# 05_Power.net
KiCad netlist of a schematic drawn in Altium Designer
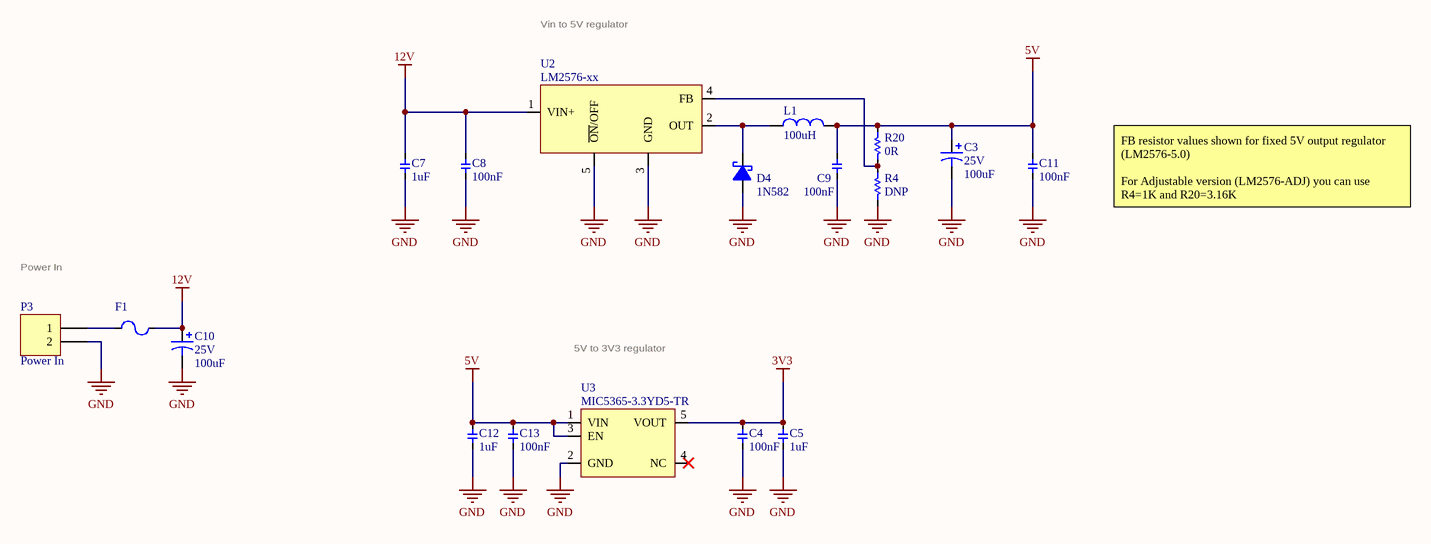
[diagram p0: 05_Power.SchDoc]

(export (version "E")
  (design (tool "Eeschema 10.0.6"))
  (components
    (comp (ref "C3")
      (value "25V")
      (footprint "Footprint_Misc:Electrolytic Cap 2.54mm")
      (description "Polarized Capacitor (Axial)")
      (fields
        (field (name "MANUFACTURER") "Würth Elektronik")
        (field (name "MANUFACTURER PART NUMBER") "860160674021")
        (field (name "ALTIUM_VALUE") "100uF")
      )
      (libsource (lib "Schematic_Misc") (part "Cap Electrolytic"))
    )
    (comp (ref "C4")
      (value "100nF")
      (footprint "Footprint_Misc:0603 - CAP")
      (description "Capacitor")
      (fields
        (field (name "MANUFACTURER") "Samsung Electro-Mechanics")
        (field (name "MANUFACTURER PART NUMBER") "CL10B103KB8NNNC")
      )
      (libsource (lib "Schematic_Misc") (part "Cap"))
    )
    (comp (ref "C5")
      (value "1uF")
      (footprint "Footprint_Misc:0603 - CAP")
      (description "Capacitor")
      (fields
        (field (name "MANUFACTURER") "Samsung Electro-Mechanics")
        (field (name "MANUFACTURER PART NUMBER") "CL10A105KB8NNNC")
      )
      (libsource (lib "Schematic_Misc") (part "Cap"))
    )
    (comp (ref "C7")
      (value "1uF")
      (footprint "Footprint_Misc:0603 - CAP")
      (description "Capacitor")
      (fields
        (field (name "MANUFACTURER") "Samsung Electro-Mechanics")
        (field (name "MANUFACTURER PART NUMBER") "CL10A105KB8NNNC")
      )
      (libsource (lib "Schematic_Misc") (part "Cap"))
    )
    (comp (ref "C8")
      (value "100nF")
      (footprint "Footprint_Misc:0603 - CAP")
      (description "Capacitor")
      (fields
        (field (name "MANUFACTURER") "Samsung Electro-Mechanics")
        (field (name "MANUFACTURER PART NUMBER") "CL10B103KB8NNNC")
      )
      (libsource (lib "Schematic_Misc") (part "Cap"))
    )
    (comp (ref "C9")
      (value "100nF")
      (footprint "Footprint_Misc:0603 - CAP")
      (description "Capacitor")
      (fields
        (field (name "MANUFACTURER") "Samsung Electro-Mechanics")
        (field (name "MANUFACTURER PART NUMBER") "CL10B103KB8NNNC")
      )
      (libsource (lib "Schematic_Misc") (part "Cap"))
    )
    (comp (ref "C10")
      (value "25V")
      (footprint "Footprint_Misc:Electrolytic Cap 2.54mm")
      (description "Polarized Capacitor (Axial)")
      (fields
        (field (name "MANUFACTURER") "Würth Elektronik")
        (field (name "MANUFACTURER PART NUMBER") "860160674021")
        (field (name "ALTIUM_VALUE") "100uF")
      )
      (libsource (lib "Schematic_Misc") (part "Cap Electrolytic"))
    )
    (comp (ref "C11")
      (value "100nF")
      (footprint "Footprint_Misc:0603 - CAP")
      (description "Capacitor")
      (fields
        (field (name "MANUFACTURER") "Samsung Electro-Mechanics")
        (field (name "MANUFACTURER PART NUMBER") "CL10B103KB8NNNC")
      )
      (libsource (lib "Schematic_Misc") (part "Cap"))
    )
    (comp (ref "C12")
      (value "1uF")
      (footprint "Footprint_Misc:0603 - CAP")
      (description "Capacitor")
      (fields
        (field (name "MANUFACTURER") "Samsung Electro-Mechanics")
        (field (name "MANUFACTURER PART NUMBER") "CL10A105KB8NNNC")
      )
      (libsource (lib "Schematic_Misc") (part "Cap"))
    )
    (comp (ref "C13")
      (value "100nF")
      (footprint "Footprint_Misc:0603 - CAP")
      (description "Capacitor")
      (fields
        (field (name "MANUFACTURER") "Samsung Electro-Mechanics")
        (field (name "MANUFACTURER PART NUMBER") "CL10B103KB8NNNC")
      )
      (libsource (lib "Schematic_Misc") (part "Cap"))
    )
    (comp (ref "D4")
      (value "1N582")
      (footprint "Moji Footprintovi:SOD123F")
      (fields
        (field (name "MANUFACTURER") "Nexperia USA Inc.")
        (field (name "MANUFACTURER PART NUMBER") "PMEG6010CEH,115")
        (field (name "DISTRIBUTOR PART NUMBER") "1727-3848-1-ND")
      )
      (libsource (lib "Moji Schematici (1)") (part "Diode Schotky"))
    )
    (comp (ref "F1")
      (value "Fuse Thermal")
      (footprint "Moji Footprintovi:1812F")
      (description "Thermal Fuse")
      (fields
        (field (name "DISTRIBUTOR PART NUMBER") "SF-1206SP200-2CT-ND")
        (field (name "MANUFACTURER") "Bourns Inc.")
      )
      (libsource (lib "Moji Schematici (1)") (part "Fuse Thermal"))
    )
    (comp (ref "L1")
      (value "100uH")
      (footprint "Moji Footprintovi:IND_TH_SMD")
      (description "Inductor")
      (fields
        (field (name "MANUFACTURER") "TDK Corporation")
        (field (name "MANUFACTURER PART NUMBER") "VLS6045AF-101M")
      )
      (libsource (lib "Schematic_Misc") (part "Inductor"))
    )
    (comp (ref "P3")
      (value "Power In")
      (footprint "Moji Footprintovi:Header 2x1")
      (description "Header, 2-Pin")
      (libsource (lib "Moji Schematici (1)") (part "Header 2"))
    )
    (comp (ref "R4")
      (value "DNP")
      (footprint "Footprint_Misc:0603 - HS")
      (description "Resistor")
      (fields (field (name "Comment") "Res"))
      (libsource (lib "Moji Schematici (1)") (part "Res"))
    )
    (comp (ref "R20")
      (value "0R")
      (footprint "Footprint_Misc:0603 - HS")
      (description "Resistor")
      (fields
        (field (name "DISTRIBUTOR PART NUMBER") "RMCF0603ZT0R00CT-ND")
        (field (name "MANUFACTURER") "Stackpole Electronics Inc")
      )
      (libsource (lib "Moji Schematici (1)") (part "Res"))
    )
    (comp (ref "U2")
      (value "LM2576-xx")
      (footprint "Footprint_Misc:TO263-5")
      (description "Switching mode regulator [ 3v3, 5v, 12v and ADJ ]")
      (fields
        (field (name "DISTRIBUTOR PART NUMBER") "LM2576S-5.0/NOPB-ND")
        (field (name "MANUFACTURER") "Texas Instruments")
      )
      (libsource (lib "Schematic_Misc") (part "LM2576-xx"))
    )
    (comp (ref "U3")
      (value "MIC5365-3.3YD5-TR")
      (footprint "Moji Footprintovi:SOT-23-5 - duplicate")
      (description "IC REG LIN 3.3V 150MA TSOT23-5")
      (fields
        (field (name "DISTRIBUTOR PART NUMBER") "576-4085-1-ND")
        (field (name "MANUFACTURER") "Microchip Technology")
      )
      (libsource (lib "Schematic_Misc") (part "MIC5365-1.8YD5-TR"))
    )
  )
  (nets
    (net (code "1") (name "3V3") (class "Default")
      (node (ref "C4") (pin "2") (pinfunction "2_2") (pintype "passive"))
      (node (ref "C5") (pin "2") (pinfunction "2_2") (pintype "passive"))
      (node (ref "U3") (pin "5") (pinfunction "VOUT_5") (pintype "passive"))
    )
    (net (code "2") (name "5V") (class "Default")
      (node (ref "C11") (pin "2") (pinfunction "2_2") (pintype "passive"))
      (node (ref "C12") (pin "2") (pinfunction "2_2") (pintype "passive"))
      (node (ref "C13") (pin "2") (pinfunction "2_2") (pintype "passive"))
      (node (ref "C3") (pin "1") (pinfunction "1_1") (pintype "passive"))
      (node (ref "C9") (pin "2") (pinfunction "2_2") (pintype "passive"))
      (node (ref "L1") (pin "2") (pinfunction "2_2") (pintype "passive"))
      (node (ref "R20") (pin "2") (pinfunction "2_2") (pintype "passive"))
      (node (ref "U3") (pin "1") (pinfunction "VIN_1") (pintype "passive"))
      (node (ref "U3") (pin "3") (pinfunction "EN_3") (pintype "passive"))
    )
    (net (code "3") (name "12V") (class "Default")
      (node (ref "C10") (pin "1") (pinfunction "1_1") (pintype "passive"))
      (node (ref "C7") (pin "2") (pinfunction "2_2") (pintype "passive"))
      (node (ref "C8") (pin "2") (pinfunction "2_2") (pintype "passive"))
      (node (ref "F1") (pin "1") (pinfunction "1_1") (pintype "passive"))
      (node (ref "U2") (pin "1") (pinfunction "VIN+_1") (pintype "passive"))
    )
    (net (code "4") (name "GND") (class "Default")
      (node (ref "C10") (pin "2") (pinfunction "2_2") (pintype "passive"))
      (node (ref "C11") (pin "1") (pinfunction "1_1") (pintype "passive"))
      (node (ref "C12") (pin "1") (pinfunction "1_1") (pintype "passive"))
      (node (ref "C13") (pin "1") (pinfunction "1_1") (pintype "passive"))
      (node (ref "C3") (pin "2") (pinfunction "2_2") (pintype "passive"))
      (node (ref "C4") (pin "1") (pinfunction "1_1") (pintype "passive"))
      (node (ref "C5") (pin "1") (pinfunction "1_1") (pintype "passive"))
      (node (ref "C7") (pin "1") (pinfunction "1_1") (pintype "passive"))
      (node (ref "C8") (pin "1") (pinfunction "1_1") (pintype "passive"))
      (node (ref "C9") (pin "1") (pinfunction "1_1") (pintype "passive"))
      (node (ref "D4") (pin "A") (pinfunction "A_A") (pintype "passive"))
      (node (ref "P3") (pin "2") (pinfunction "2_2") (pintype "passive"))
      (node (ref "R4") (pin "1") (pinfunction "1_1") (pintype "passive"))
      (node (ref "U2") (pin "3") (pinfunction "GND_3") (pintype "passive"))
      (node (ref "U2") (pin "5") (pinfunction "~{ON}/OFF_5") (pintype "passive"))
      (node (ref "U3") (pin "2") (pinfunction "GND_2") (pintype "passive"))
    )
    (net (code "5") (name "Net-(F1-Pad2)") (class "Default")
      (node (ref "F1") (pin "2") (pinfunction "2_2") (pintype "passive"))
      (node (ref "P3") (pin "1") (pinfunction "1_1") (pintype "passive"))
    )
    (net (code "6") (name "Net-(U2-FB)") (class "Default")
      (node (ref "R20") (pin "1") (pinfunction "1_1") (pintype "passive"))
      (node (ref "R4") (pin "2") (pinfunction "2_2") (pintype "passive"))
      (node (ref "U2") (pin "4") (pinfunction "FB_4") (pintype "passive"))
    )
    (net (code "7") (name "Net-(U2-OUT)") (class "Default")
      (node (ref "D4") (pin "K") (pinfunction "K_K") (pintype "passive"))
      (node (ref "L1") (pin "1") (pinfunction "1_1") (pintype "passive"))
      (node (ref "U2") (pin "2") (pinfunction "OUT_2") (pintype "passive"))
    )
    (net (code "8") (name "unconnected-(U3-NC-Pad4)") (class "Default")
      (node (ref "U3") (pin "4") (pinfunction "NC_4") (pintype "passive+no_connect"))
    )
  )
)
